# pir.net
KiCad netlist of a schematic drawn in EAGLE
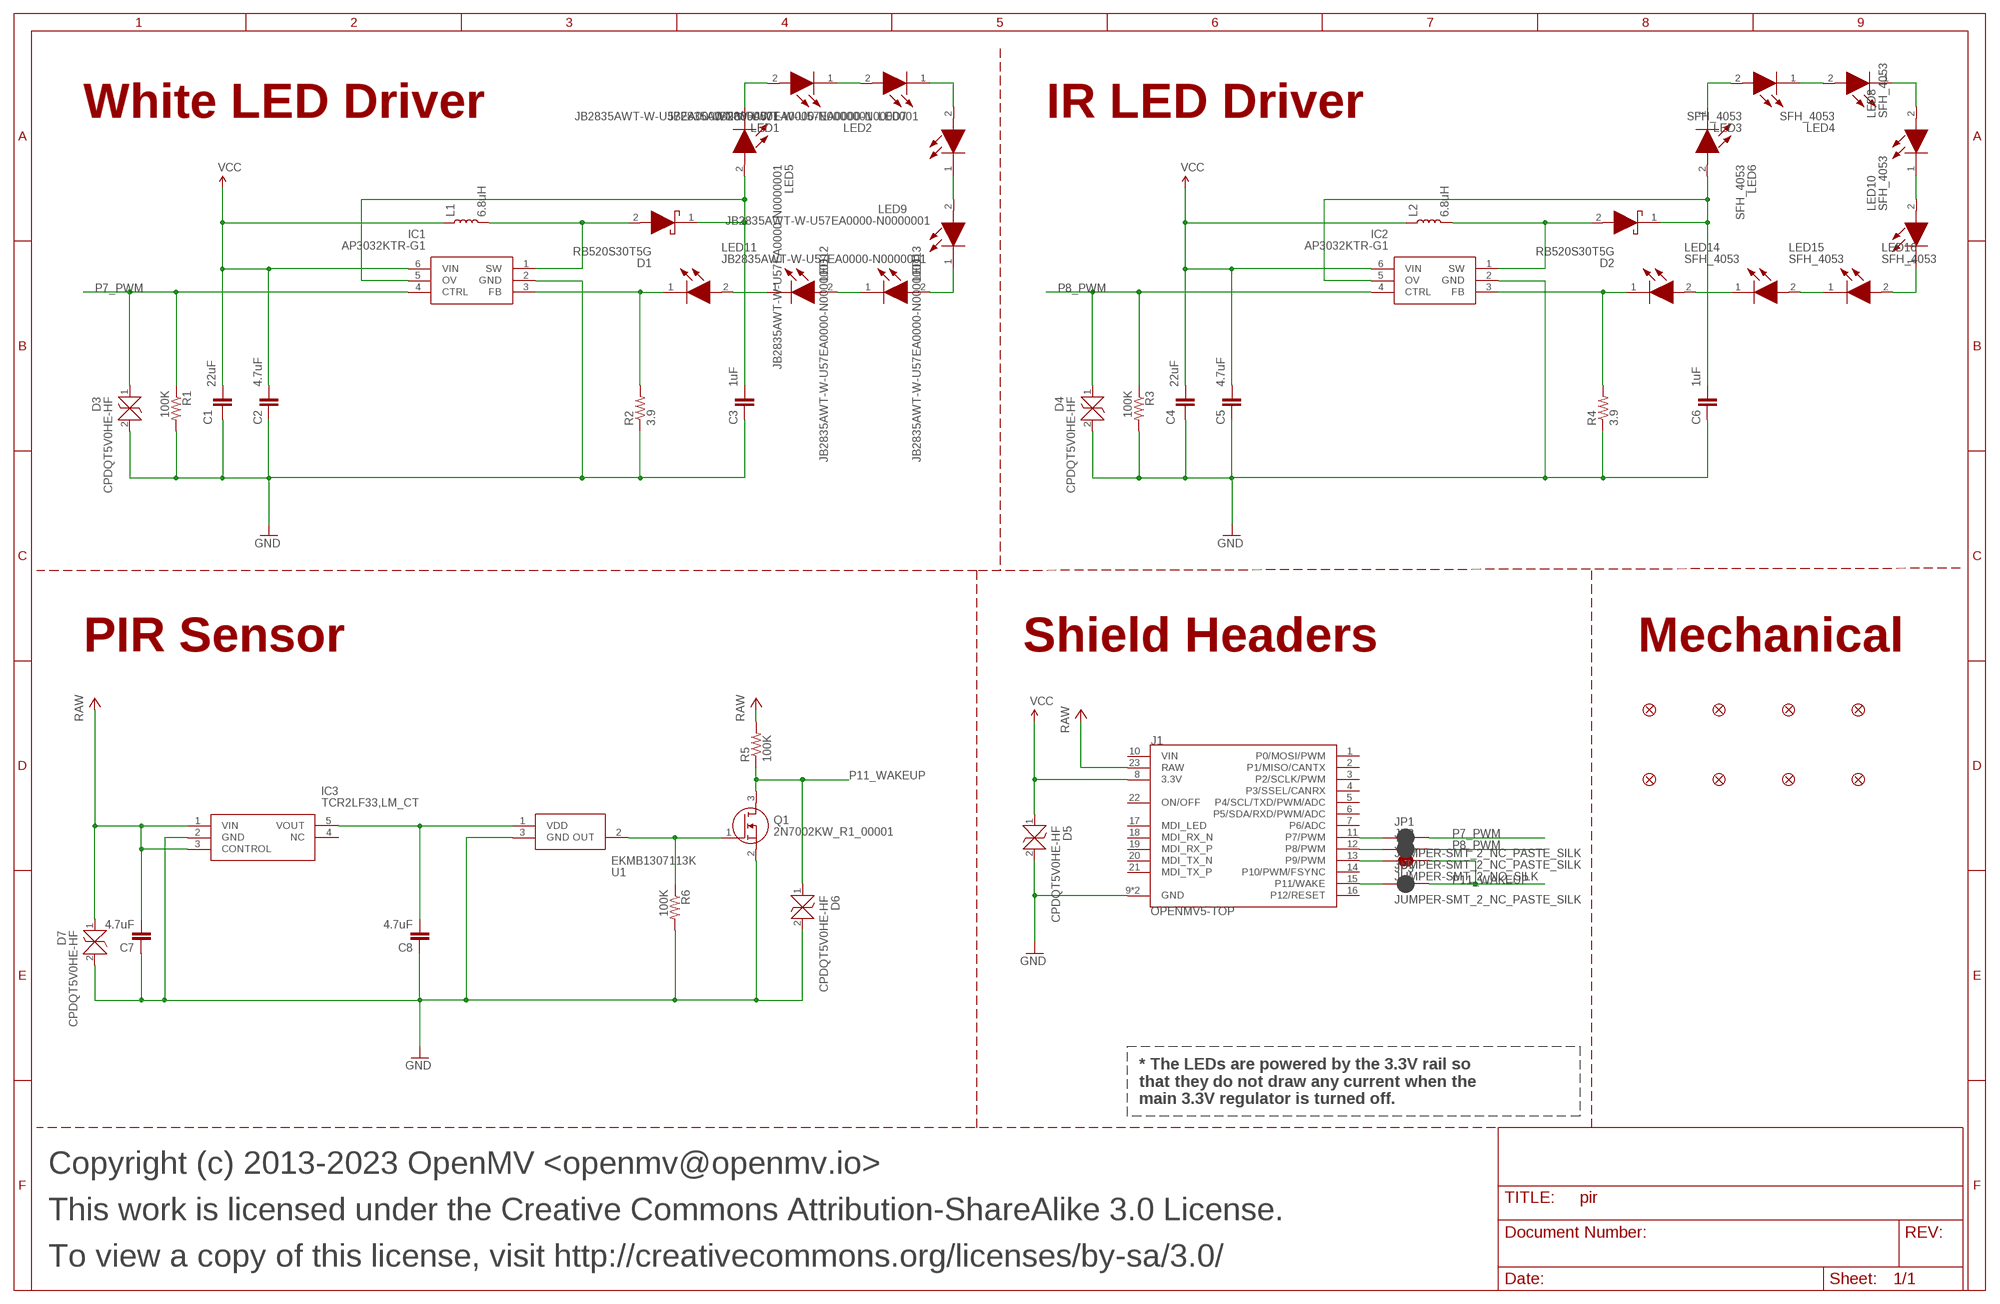
[diagram p0: schematic, sheet 1]

(export (version "E")
  (design (tool "Eeschema 10.0.6"))
  (components
    (comp (ref "C1")
      (value "22uF")
      (footprint "eagle-import:0805")
      (fields (field (name "MPN") "CL21A226MQQNNNE"))
      (libsource (lib "eagle-import") (part "22UF-0805-6.3V-20%"))
    )
    (comp (ref "C2")
      (value "4.7uF")
      (footprint "eagle-import:0402-CAP")
      (fields (field (name "MPN") "JMK105BBJ475MV-F"))
      (libsource (lib "eagle-import") (part "CAP0402-CAP"))
    )
    (comp (ref "C3")
      (value "1uF")
      (footprint "eagle-import:0402-CAP")
      (fields (field (name "MPN") "GRM155R6YA105KE11D"))
      (libsource (lib "eagle-import") (part "CAP0402-CAP"))
    )
    (comp (ref "C4")
      (value "22uF")
      (footprint "eagle-import:0805")
      (fields (field (name "MPN") "CL21A226MQQNNNE"))
      (libsource (lib "eagle-import") (part "22UF-0805-6.3V-20%"))
    )
    (comp (ref "C5")
      (value "4.7uF")
      (footprint "eagle-import:0402-CAP")
      (fields (field (name "MPN") "JMK105BBJ475MV-F"))
      (libsource (lib "eagle-import") (part "CAP0402-CAP"))
    )
    (comp (ref "C6")
      (value "1uF")
      (footprint "eagle-import:0402-CAP")
      (fields (field (name "MPN") "GRM155R6YA105KE11D"))
      (libsource (lib "eagle-import") (part "CAP0402-CAP"))
    )
    (comp (ref "C7")
      (value "4.7uF")
      (footprint "eagle-import:0402-CAP")
      (fields (field (name "MPN") "JMK105BBJ475MV-F"))
      (libsource (lib "eagle-import") (part "CAP0402-CAP"))
    )
    (comp (ref "C8")
      (value "4.7uF")
      (footprint "eagle-import:0402-CAP")
      (fields (field (name "MPN") "JMK105BBJ475MV-F"))
      (libsource (lib "eagle-import") (part "CAP0402-CAP"))
    )
    (comp (ref "D1")
      (value "RB520S30T5G")
      (footprint "eagle-import:SODFL1608X70N")
      (fields (field (name "MOUSER_PART_NUMBER") "863-RB520S30T5G"))
      (libsource (lib "eagle-import") (part "RB520S30T5G"))
    )
    (comp (ref "D2")
      (value "RB520S30T5G")
      (footprint "eagle-import:SODFL1608X70N")
      (fields (field (name "MOUSER_PART_NUMBER") "863-RB520S30T5G"))
      (libsource (lib "eagle-import") (part "RB520S30T5G"))
    )
    (comp (ref "D3")
      (value "CPDQT5V0HE-HF")
      (footprint "eagle-import:CPDQT5V0HEHF")
      (libsource (lib "eagle-import") (part "CPDQT5V0HE-HF"))
    )
    (comp (ref "D4")
      (value "CPDQT5V0HE-HF")
      (footprint "eagle-import:CPDQT5V0HEHF")
      (libsource (lib "eagle-import") (part "CPDQT5V0HE-HF"))
    )
    (comp (ref "D5")
      (value "CPDQT5V0HE-HF")
      (footprint "eagle-import:CPDQT5V0HEHF")
      (libsource (lib "eagle-import") (part "CPDQT5V0HE-HF"))
    )
    (comp (ref "D6")
      (value "CPDQT5V0HE-HF")
      (footprint "eagle-import:CPDQT5V0HEHF")
      (libsource (lib "eagle-import") (part "CPDQT5V0HE-HF"))
    )
    (comp (ref "D7")
      (value "CPDQT5V0HE-HF")
      (footprint "eagle-import:CPDQT5V0HEHF")
      (libsource (lib "eagle-import") (part "CPDQT5V0HE-HF"))
    )
    (comp (ref "FD1")
      (value "FIDUCIAL1X2")
      (footprint "eagle-import:FIDUCIAL-1X2")
      (libsource (lib "eagle-import") (part "FIDUCIAL1X2"))
    )
    (comp (ref "FD2")
      (value "FIDUCIAL1X2")
      (footprint "eagle-import:FIDUCIAL-1X2")
      (libsource (lib "eagle-import") (part "FIDUCIAL1X2"))
    )
    (comp (ref "FD3")
      (value "FIDUCIAL1X2")
      (footprint "eagle-import:FIDUCIAL-1X2")
      (libsource (lib "eagle-import") (part "FIDUCIAL1X2"))
    )
    (comp (ref "FD4")
      (value "FIDUCIAL1X2")
      (footprint "eagle-import:FIDUCIAL-1X2")
      (libsource (lib "eagle-import") (part "FIDUCIAL1X2"))
    )
    (comp (ref "FD5")
      (value "FIDUCIAL1X2")
      (footprint "eagle-import:FIDUCIAL-1X2")
      (libsource (lib "eagle-import") (part "FIDUCIAL1X2"))
    )
    (comp (ref "FD6")
      (value "FIDUCIAL1X2")
      (footprint "eagle-import:FIDUCIAL-1X2")
      (libsource (lib "eagle-import") (part "FIDUCIAL1X2"))
    )
    (comp (ref "FD7")
      (value "FIDUCIAL1X2")
      (footprint "eagle-import:FIDUCIAL-1X2")
      (libsource (lib "eagle-import") (part "FIDUCIAL1X2"))
    )
    (comp (ref "FD8")
      (value "FIDUCIAL1X2")
      (footprint "eagle-import:FIDUCIAL-1X2")
      (libsource (lib "eagle-import") (part "FIDUCIAL1X2"))
    )
    (comp (ref "IC1")
      (value "AP3032KTR-G1")
      (footprint "eagle-import:SOT95P280X145-6N")
      (fields (field (name "MOUSER_PART_NUMBER") "621-AP3032KTR-G1"))
      (libsource (lib "eagle-import") (part "AP3032KTR-G1"))
    )
    (comp (ref "IC2")
      (value "AP3032KTR-G1")
      (footprint "eagle-import:SOT95P280X145-6N")
      (fields (field (name "MOUSER_PART_NUMBER") "621-AP3032KTR-G1"))
      (libsource (lib "eagle-import") (part "AP3032KTR-G1"))
    )
    (comp (ref "IC3")
      (value "TCR2LF33,LM_CT")
      (footprint "eagle-import:TCR2LF33LMCT")
      (fields
        (field (name "MANUFACTURER_PART_NUMBER") "TCR2LF33,LM(CT")
        (field (name "MOUSER_PART_NUMBER") "757-TCR2LF33LMCT")
      )
      (libsource (lib "eagle-import") (part "TCR2LF33,LM_CT"))
    )
    (comp (ref "J1")
      (value "OPENMV5-TOP")
      (footprint "eagle-import:OPENMV5-TOP")
      (libsource (lib "eagle-import") (part "OPENMV5-TOP"))
    )
    (comp (ref "JP1")
      (value "JUMPER-SMT_2_NC_PASTE_SILK")
      (footprint "eagle-import:SMT-JUMPER_2_NC_PASTE_SILK")
      (libsource (lib "eagle-import") (part "JUMPER-SMT_2_NC_PASTE_SILK"))
    )
    (comp (ref "JP2")
      (value "JUMPER-SMT_2_NC_PASTE_SILK")
      (footprint "eagle-import:SMT-JUMPER_2_NC_PASTE_SILK")
      (libsource (lib "eagle-import") (part "JUMPER-SMT_2_NC_PASTE_SILK"))
    )
    (comp (ref "JP3")
      (value "JUMPER-SMT_2_NC_PASTE_SILK")
      (footprint "eagle-import:SMT-JUMPER_2_NC_PASTE_SILK")
      (libsource (lib "eagle-import") (part "JUMPER-SMT_2_NC_PASTE_SILK"))
    )
    (comp (ref "JP4")
      (value "JUMPER-SMT_2_NO_SILK")
      (footprint "eagle-import:SMT-JUMPER_2_NO_SILK")
      (libsource (lib "eagle-import") (part "JUMPER-SMT_2_NO_SILK"))
    )
    (comp (ref "L1")
      (value "6.8uH")
      (footprint "eagle-import:0805")
      (fields (field (name "MPN") "MLZ2012M6R8WT000"))
      (libsource (lib "eagle-import") (part "INDUCTOR-0805-3.3UH"))
    )
    (comp (ref "L2")
      (value "6.8uH")
      (footprint "eagle-import:0805")
      (fields (field (name "MPN") "MLZ2012M6R8WT000"))
      (libsource (lib "eagle-import") (part "INDUCTOR-0805-3.3UH"))
    )
    (comp (ref "LED1")
      (value "JB2835AWT-W-U57EA0000-N0000001")
      (footprint "eagle-import:JB2835AWTWU57EA0000N0000001")
      (fields (field (name "MOUSER_PART_NUMBER") "941-JB2835AWTU57EAN"))
      (libsource (lib "eagle-import") (part "JB2835AWT-W-U57EA0000-N0000001"))
    )
    (comp (ref "LED2")
      (value "JB2835AWT-W-U57EA0000-N0000001")
      (footprint "eagle-import:JB2835AWTWU57EA0000N0000001")
      (fields (field (name "MOUSER_PART_NUMBER") "941-JB2835AWTU57EAN"))
      (libsource (lib "eagle-import") (part "JB2835AWT-W-U57EA0000-N0000001"))
    )
    (comp (ref "LED3")
      (value "SFH_4053")
      (footprint "eagle-import:LEDC1005X55N")
      (fields
        (field (name "MANUFACTURER_PART_NUMBER") "SFH 4053")
        (field (name "MOUSER_PART_NUMBER") "720-SFH4053")
      )
      (libsource (lib "eagle-import") (part "SFH_4053"))
    )
    (comp (ref "LED4")
      (value "SFH_4053")
      (footprint "eagle-import:LEDC1005X55N")
      (fields
        (field (name "MANUFACTURER_PART_NUMBER") "SFH 4053")
        (field (name "MOUSER_PART_NUMBER") "720-SFH4053")
      )
      (libsource (lib "eagle-import") (part "SFH_4053"))
    )
    (comp (ref "LED5")
      (value "JB2835AWT-W-U57EA0000-N0000001")
      (footprint "eagle-import:JB2835AWTWU57EA0000N0000001")
      (fields (field (name "MOUSER_PART_NUMBER") "941-JB2835AWTU57EAN"))
      (libsource (lib "eagle-import") (part "JB2835AWT-W-U57EA0000-N0000001"))
    )
    (comp (ref "LED6")
      (value "SFH_4053")
      (footprint "eagle-import:LEDC1005X55N")
      (fields
        (field (name "MANUFACTURER_PART_NUMBER") "SFH 4053")
        (field (name "MOUSER_PART_NUMBER") "720-SFH4053")
      )
      (libsource (lib "eagle-import") (part "SFH_4053"))
    )
    (comp (ref "LED7")
      (value "JB2835AWT-W-U57EA0000-N0000001")
      (footprint "eagle-import:JB2835AWTWU57EA0000N0000001")
      (fields (field (name "MOUSER_PART_NUMBER") "941-JB2835AWTU57EAN"))
      (libsource (lib "eagle-import") (part "JB2835AWT-W-U57EA0000-N0000001"))
    )
    (comp (ref "LED8")
      (value "SFH_4053")
      (footprint "eagle-import:LEDC1005X55N")
      (fields
        (field (name "MANUFACTURER_PART_NUMBER") "SFH 4053")
        (field (name "MOUSER_PART_NUMBER") "720-SFH4053")
      )
      (libsource (lib "eagle-import") (part "SFH_4053"))
    )
    (comp (ref "LED9")
      (value "JB2835AWT-W-U57EA0000-N0000001")
      (footprint "eagle-import:JB2835AWTWU57EA0000N0000001")
      (fields (field (name "MOUSER_PART_NUMBER") "941-JB2835AWTU57EAN"))
      (libsource (lib "eagle-import") (part "JB2835AWT-W-U57EA0000-N0000001"))
    )
    (comp (ref "LED10")
      (value "SFH_4053")
      (footprint "eagle-import:LEDC1005X55N")
      (fields
        (field (name "MANUFACTURER_PART_NUMBER") "SFH 4053")
        (field (name "MOUSER_PART_NUMBER") "720-SFH4053")
      )
      (libsource (lib "eagle-import") (part "SFH_4053"))
    )
    (comp (ref "LED11")
      (value "JB2835AWT-W-U57EA0000-N0000001")
      (footprint "eagle-import:JB2835AWTWU57EA0000N0000001")
      (fields (field (name "MOUSER_PART_NUMBER") "941-JB2835AWTU57EAN"))
      (libsource (lib "eagle-import") (part "JB2835AWT-W-U57EA0000-N0000001"))
    )
    (comp (ref "LED12")
      (value "JB2835AWT-W-U57EA0000-N0000001")
      (footprint "eagle-import:JB2835AWTWU57EA0000N0000001")
      (fields (field (name "MOUSER_PART_NUMBER") "941-JB2835AWTU57EAN"))
      (libsource (lib "eagle-import") (part "JB2835AWT-W-U57EA0000-N0000001"))
    )
    (comp (ref "LED13")
      (value "JB2835AWT-W-U57EA0000-N0000001")
      (footprint "eagle-import:JB2835AWTWU57EA0000N0000001")
      (fields (field (name "MOUSER_PART_NUMBER") "941-JB2835AWTU57EAN"))
      (libsource (lib "eagle-import") (part "JB2835AWT-W-U57EA0000-N0000001"))
    )
    (comp (ref "LED14")
      (value "SFH_4053")
      (footprint "eagle-import:LEDC1005X55N")
      (fields
        (field (name "MANUFACTURER_PART_NUMBER") "SFH 4053")
        (field (name "MOUSER_PART_NUMBER") "720-SFH4053")
      )
      (libsource (lib "eagle-import") (part "SFH_4053"))
    )
    (comp (ref "LED15")
      (value "SFH_4053")
      (footprint "eagle-import:LEDC1005X55N")
      (fields
        (field (name "MANUFACTURER_PART_NUMBER") "SFH 4053")
        (field (name "MOUSER_PART_NUMBER") "720-SFH4053")
      )
      (libsource (lib "eagle-import") (part "SFH_4053"))
    )
    (comp (ref "LED16")
      (value "SFH_4053")
      (footprint "eagle-import:LEDC1005X55N")
      (fields
        (field (name "MANUFACTURER_PART_NUMBER") "SFH 4053")
        (field (name "MOUSER_PART_NUMBER") "720-SFH4053")
      )
      (libsource (lib "eagle-import") (part "SFH_4053"))
    )
    (comp (ref "Q1")
      (value "2N7002KW_R1_00001")
      (footprint "eagle-import:SOT65P210X110-3N")
      (fields (field (name "MOUSER_PART_NUMBER") "241-2N7002KWR100001"))
      (libsource (lib "eagle-import") (part "2N7002KW_R1_00001"))
    )
    (comp (ref "R1")
      (value "100K")
      (footprint "eagle-import:0402-RES")
      (fields (field (name "MPN") "AC0402FR-07100KL"))
      (libsource (lib "eagle-import") (part "RESISTOR0402-RES"))
    )
    (comp (ref "R2")
      (value "3.9")
      (footprint "eagle-import:R2512")
      (fields (field (name "MPN") "35203R9JT"))
      (libsource (lib "eagle-import") (part "R-US_R2512"))
    )
    (comp (ref "R3")
      (value "100K")
      (footprint "eagle-import:0402-RES")
      (fields (field (name "MPN") "AC0402FR-07100KL"))
      (libsource (lib "eagle-import") (part "RESISTOR0402-RES"))
    )
    (comp (ref "R4")
      (value "3.9")
      (footprint "eagle-import:R2512")
      (fields (field (name "MPN") "35203R9JT"))
      (libsource (lib "eagle-import") (part "R-US_R2512"))
    )
    (comp (ref "R5")
      (value "100K")
      (footprint "eagle-import:0402-RES")
      (fields (field (name "MPN") "AC0402FR-07100KL"))
      (libsource (lib "eagle-import") (part "RESISTOR0402-RES"))
    )
    (comp (ref "R6")
      (value "100K")
      (footprint "eagle-import:0402-RES")
      (fields (field (name "MPN") "AC0402FR-07100KL"))
      (libsource (lib "eagle-import") (part "RESISTOR0402-RES"))
    )
    (comp (ref "U1")
      (value "EKMB1307113K")
      (footprint "eagle-import:EKMB1304111K")
      (fields
        (field (name "MANUFACTURER_PART_NUMBER") "EKMB1304111K")
        (field (name "MOUSER_PART_NUMBER") "769-EKMB1304111K")
      )
      (libsource (lib "eagle-import") (part "EKMB1304111K"))
    )
  )
  (nets
    (net (code "1") (name "/P7_PWM") (class "Default")
      (node (ref "D3") (pin "1") (pinfunction "1_1") (pintype "bidirectional"))
      (node (ref "IC1") (pin "4") (pinfunction "CTRL_4") (pintype "bidirectional"))
      (node (ref "JP1") (pin "2") (pinfunction "2_2") (pintype "passive"))
      (node (ref "R1") (pin "1") (pinfunction "1_1") (pintype "passive"))
    )
    (net (code "2") (name "/P8_PWM") (class "Default")
      (node (ref "D4") (pin "1") (pinfunction "1_1") (pintype "bidirectional"))
      (node (ref "IC2") (pin "4") (pinfunction "CTRL_4") (pintype "bidirectional"))
      (node (ref "JP2") (pin "2") (pinfunction "2_2") (pintype "passive"))
      (node (ref "R3") (pin "1") (pinfunction "1_1") (pintype "passive"))
    )
    (net (code "3") (name "/P11_WAKEUP") (class "Default")
      (node (ref "D6") (pin "1") (pinfunction "1_1") (pintype "bidirectional"))
      (node (ref "JP3") (pin "2") (pinfunction "2_2") (pintype "passive"))
      (node (ref "JP4") (pin "2") (pinfunction "2_2") (pintype "passive"))
      (node (ref "Q1") (pin "3") (pinfunction "D_3") (pintype "bidirectional"))
      (node (ref "R5") (pin "1") (pinfunction "1_1") (pintype "passive"))
    )
    (net (code "4") (name "/VIN") (class "Default")
      (node (ref "J1") (pin "10") (pinfunction "VIN_10") (pintype "power_in"))
    )
    (net (code "5") (name "GND") (class "Default")
      (node (ref "C1") (pin "1") (pinfunction "1_1") (pintype "passive"))
      (node (ref "C2") (pin "1") (pinfunction "1_1") (pintype "passive"))
      (node (ref "C3") (pin "1") (pinfunction "1_1") (pintype "passive"))
      (node (ref "C4") (pin "1") (pinfunction "1_1") (pintype "passive"))
      (node (ref "C5") (pin "1") (pinfunction "1_1") (pintype "passive"))
      (node (ref "C6") (pin "1") (pinfunction "1_1") (pintype "passive"))
      (node (ref "C7") (pin "1") (pinfunction "1_1") (pintype "passive"))
      (node (ref "C8") (pin "1") (pinfunction "1_1") (pintype "passive"))
      (node (ref "D3") (pin "2") (pinfunction "2_2") (pintype "bidirectional"))
      (node (ref "D4") (pin "2") (pinfunction "2_2") (pintype "bidirectional"))
      (node (ref "D5") (pin "2") (pinfunction "2_2") (pintype "bidirectional"))
      (node (ref "D6") (pin "2") (pinfunction "2_2") (pintype "bidirectional"))
      (node (ref "D7") (pin "2") (pinfunction "2_2") (pintype "bidirectional"))
      (node (ref "IC1") (pin "2") (pinfunction "GND_2") (pintype "bidirectional"))
      (node (ref "IC2") (pin "2") (pinfunction "GND_2") (pintype "bidirectional"))
      (node (ref "IC3") (pin "2") (pinfunction "GND_2") (pintype "bidirectional"))
      (node (ref "J1") (pin "24") (pinfunction "GND_24") (pintype "power_in"))
      (node (ref "J1") (pin "9") (pinfunction "GND_9") (pintype "power_in"))
      (node (ref "Q1") (pin "2") (pinfunction "S_2") (pintype "bidirectional"))
      (node (ref "R1") (pin "2") (pinfunction "2_2") (pintype "passive"))
      (node (ref "R2") (pin "1") (pinfunction "1_1") (pintype "passive"))
      (node (ref "R3") (pin "2") (pinfunction "2_2") (pintype "passive"))
      (node (ref "R4") (pin "1") (pinfunction "1_1") (pintype "passive"))
      (node (ref "R6") (pin "2") (pinfunction "2_2") (pintype "passive"))
      (node (ref "U1") (pin "3") (pinfunction "GND_3") (pintype "bidirectional"))
    )
    (net (code "6") (name "Net-(D1-A)") (class "Default")
      (node (ref "D1") (pin "2") (pinfunction "A_2") (pintype "bidirectional"))
      (node (ref "IC1") (pin "1") (pinfunction "SW_1") (pintype "bidirectional"))
      (node (ref "L1") (pin "2") (pinfunction "2_2") (pintype "passive"))
    )
    (net (code "7") (name "Net-(D1-K)") (class "Default")
      (node (ref "C3") (pin "2") (pinfunction "2_2") (pintype "passive"))
      (node (ref "D1") (pin "1") (pinfunction "K_1") (pintype "bidirectional"))
      (node (ref "IC1") (pin "5") (pinfunction "OV_5") (pintype "bidirectional"))
      (node (ref "LED5") (pin "2") (pinfunction "A_2") (pintype "bidirectional"))
    )
    (net (code "8") (name "Net-(D2-A)") (class "Default")
      (node (ref "D2") (pin "2") (pinfunction "A_2") (pintype "bidirectional"))
      (node (ref "IC2") (pin "1") (pinfunction "SW_1") (pintype "bidirectional"))
      (node (ref "L2") (pin "2") (pinfunction "2_2") (pintype "passive"))
    )
    (net (code "9") (name "Net-(D2-K)") (class "Default")
      (node (ref "C6") (pin "2") (pinfunction "2_2") (pintype "passive"))
      (node (ref "D2") (pin "1") (pinfunction "K_1") (pintype "bidirectional"))
      (node (ref "IC2") (pin "5") (pinfunction "OV_5") (pintype "bidirectional"))
      (node (ref "LED6") (pin "2") (pinfunction "A_2") (pintype "bidirectional"))
    )
    (net (code "10") (name "Net-(IC1-FB)") (class "Default")
      (node (ref "IC1") (pin "3") (pinfunction "FB_3") (pintype "bidirectional"))
      (node (ref "LED11") (pin "1") (pinfunction "K_1") (pintype "bidirectional"))
      (node (ref "R2") (pin "2") (pinfunction "2_2") (pintype "passive"))
    )
    (net (code "11") (name "Net-(IC2-FB)") (class "Default")
      (node (ref "IC2") (pin "3") (pinfunction "FB_3") (pintype "bidirectional"))
      (node (ref "LED14") (pin "1") (pinfunction "K_1") (pintype "bidirectional"))
      (node (ref "R4") (pin "2") (pinfunction "2_2") (pintype "passive"))
    )
    (net (code "12") (name "Net-(IC3-VOUT)") (class "Default")
      (node (ref "C8") (pin "2") (pinfunction "2_2") (pintype "passive"))
      (node (ref "IC3") (pin "5") (pinfunction "VOUT_5") (pintype "bidirectional"))
      (node (ref "U1") (pin "1") (pinfunction "VDD_1") (pintype "bidirectional"))
    )
    (net (code "13") (name "Net-(J1-P7{slash}PWM)") (class "Default")
      (node (ref "J1") (pin "11") (pinfunction "P7/PWM_11") (pintype "bidirectional"))
      (node (ref "JP1") (pin "1") (pinfunction "1_1") (pintype "passive"))
    )
    (net (code "14") (name "Net-(J1-P8{slash}PWM)") (class "Default")
      (node (ref "J1") (pin "12") (pinfunction "P8/PWM_12") (pintype "bidirectional"))
      (node (ref "JP2") (pin "1") (pinfunction "1_1") (pintype "passive"))
    )
    (net (code "15") (name "Net-(J1-P9{slash}PWM)") (class "Default")
      (node (ref "J1") (pin "13") (pinfunction "P9/PWM_13") (pintype "bidirectional"))
      (node (ref "JP4") (pin "1") (pinfunction "1_1") (pintype "passive"))
    )
    (net (code "16") (name "Net-(J1-P11{slash}WAKE)") (class "Default")
      (node (ref "J1") (pin "15") (pinfunction "P11/WAKE_15") (pintype "bidirectional"))
      (node (ref "JP3") (pin "1") (pinfunction "1_1") (pintype "passive"))
    )
    (net (code "17") (name "Net-(LED1-A)") (class "Default")
      (node (ref "LED1") (pin "2") (pinfunction "A_2") (pintype "bidirectional"))
      (node (ref "LED5") (pin "1") (pinfunction "K_1") (pintype "bidirectional"))
    )
    (net (code "18") (name "Net-(LED1-K)") (class "Default")
      (node (ref "LED1") (pin "1") (pinfunction "K_1") (pintype "bidirectional"))
      (node (ref "LED2") (pin "2") (pinfunction "A_2") (pintype "bidirectional"))
    )
    (net (code "19") (name "Net-(LED2-K)") (class "Default")
      (node (ref "LED2") (pin "1") (pinfunction "K_1") (pintype "bidirectional"))
      (node (ref "LED7") (pin "2") (pinfunction "A_2") (pintype "bidirectional"))
    )
    (net (code "20") (name "Net-(LED3-A)") (class "Default")
      (node (ref "LED3") (pin "2") (pinfunction "A_2") (pintype "bidirectional"))
      (node (ref "LED6") (pin "1") (pinfunction "K_1") (pintype "bidirectional"))
    )
    (net (code "21") (name "Net-(LED3-K)") (class "Default")
      (node (ref "LED3") (pin "1") (pinfunction "K_1") (pintype "bidirectional"))
      (node (ref "LED4") (pin "2") (pinfunction "A_2") (pintype "bidirectional"))
    )
    (net (code "22") (name "Net-(LED4-K)") (class "Default")
      (node (ref "LED4") (pin "1") (pinfunction "K_1") (pintype "bidirectional"))
      (node (ref "LED8") (pin "2") (pinfunction "A_2") (pintype "bidirectional"))
    )
    (net (code "23") (name "Net-(LED7-K)") (class "Default")
      (node (ref "LED7") (pin "1") (pinfunction "K_1") (pintype "bidirectional"))
      (node (ref "LED9") (pin "2") (pinfunction "A_2") (pintype "bidirectional"))
    )
    (net (code "24") (name "Net-(LED10-A)") (class "Default")
      (node (ref "LED10") (pin "2") (pinfunction "A_2") (pintype "bidirectional"))
      (node (ref "LED8") (pin "1") (pinfunction "K_1") (pintype "bidirectional"))
    )
    (net (code "25") (name "Net-(LED10-K)") (class "Default")
      (node (ref "LED10") (pin "1") (pinfunction "K_1") (pintype "bidirectional"))
      (node (ref "LED16") (pin "2") (pinfunction "A_2") (pintype "bidirectional"))
    )
    (net (code "26") (name "Net-(LED11-A)") (class "Default")
      (node (ref "LED11") (pin "2") (pinfunction "A_2") (pintype "bidirectional"))
      (node (ref "LED12") (pin "1") (pinfunction "K_1") (pintype "bidirectional"))
    )
    (net (code "27") (name "Net-(LED12-A)") (class "Default")
      (node (ref "LED12") (pin "2") (pinfunction "A_2") (pintype "bidirectional"))
      (node (ref "LED13") (pin "1") (pinfunction "K_1") (pintype "bidirectional"))
    )
    (net (code "28") (name "Net-(LED13-A)") (class "Default")
      (node (ref "LED13") (pin "2") (pinfunction "A_2") (pintype "bidirectional"))
      (node (ref "LED9") (pin "1") (pinfunction "K_1") (pintype "bidirectional"))
    )
    (net (code "29") (name "Net-(LED14-A)") (class "Default")
      (node (ref "LED14") (pin "2") (pinfunction "A_2") (pintype "bidirectional"))
      (node (ref "LED15") (pin "1") (pinfunction "K_1") (pintype "bidirectional"))
    )
    (net (code "30") (name "Net-(LED15-A)") (class "Default")
      (node (ref "LED15") (pin "2") (pinfunction "A_2") (pintype "bidirectional"))
      (node (ref "LED16") (pin "1") (pinfunction "K_1") (pintype "bidirectional"))
    )
    (net (code "31") (name "Net-(Q1-G)") (class "Default")
      (node (ref "Q1") (pin "1") (pinfunction "G_1") (pintype "bidirectional"))
      (node (ref "R6") (pin "1") (pinfunction "1_1") (pintype "passive"))
      (node (ref "U1") (pin "2") (pinfunction "OUT_2") (pintype "bidirectional"))
    )
    (net (code "32") (name "RAW") (class "Default")
      (node (ref "C7") (pin "2") (pinfunction "2_2") (pintype "passive"))
      (node (ref "D7") (pin "1") (pinfunction "1_1") (pintype "bidirectional"))
      (node (ref "IC3") (pin "1") (pinfunction "VIN_1") (pintype "bidirectional"))
      (node (ref "IC3") (pin "3") (pinfunction "CONTROL_3") (pintype "bidirectional"))
      (node (ref "J1") (pin "23") (pinfunction "RAW_23") (pintype "power_in"))
      (node (ref "R5") (pin "2") (pinfunction "2_2") (pintype "passive"))
    )
    (net (code "33") (name "VCC") (class "Default")
      (node (ref "C1") (pin "2") (pinfunction "2_2") (pintype "passive"))
      (node (ref "C2") (pin "2") (pinfunction "2_2") (pintype "passive"))
      (node (ref "C4") (pin "2") (pinfunction "2_2") (pintype "passive"))
      (node (ref "C5") (pin "2") (pinfunction "2_2") (pintype "passive"))
      (node (ref "D5") (pin "1") (pinfunction "1_1") (pintype "bidirectional"))
      (node (ref "IC1") (pin "6") (pinfunction "VIN_6") (pintype "bidirectional"))
      (node (ref "IC2") (pin "6") (pinfunction "VIN_6") (pintype "bidirectional"))
      (node (ref "J1") (pin "8") (pinfunction "3.3V_8") (pintype "power_in"))
      (node (ref "L1") (pin "1") (pinfunction "1_1") (pintype "passive"))
      (node (ref "L2") (pin "1") (pinfunction "1_1") (pintype "passive"))
    )
    (net (code "34") (name "unconnected-(IC3-NC-Pad4)") (class "Default")
      (node (ref "IC3") (pin "4") (pinfunction "NC_4") (pintype "no_connect"))
    )
    (net (code "35") (name "unconnected-(J1-MDI_LED-Pad17)") (class "Default")
      (node (ref "J1") (pin "17") (pinfunction "MDI_LED_17") (pintype "bidirectional"))
    )
    (net (code "36") (name "unconnected-(J1-MDI_RX_N-Pad18)") (class "Default")
      (node (ref "J1") (pin "18") (pinfunction "MDI_RX_N_18") (pintype "bidirectional"))
    )
    (net (code "37") (name "unconnected-(J1-MDI_RX_P-Pad19)") (class "Default")
      (node (ref "J1") (pin "19") (pinfunction "MDI_RX_P_19") (pintype "bidirectional"))
    )
    (net (code "38") (name "unconnected-(J1-MDI_TX_N-Pad20)") (class "Default")
      (node (ref "J1") (pin "20") (pinfunction "MDI_TX_N_20") (pintype "bidirectional"))
    )
    (net (code "39") (name "unconnected-(J1-MDI_TX_P-Pad21)") (class "Default")
      (node (ref "J1") (pin "21") (pinfunction "MDI_TX_P_21") (pintype "bidirectional"))
    )
    (net (code "40") (name "unconnected-(J1-ON{slash}OFF-Pad22)") (class "Default")
      (node (ref "J1") (pin "22") (pinfunction "ON/OFF_22") (pintype "bidirectional"))
    )
    (net (code "41") (name "unconnected-(J1-P0{slash}MOSI{slash}PWM-Pad1)") (class "Default")
      (node (ref "J1") (pin "1") (pinfunction "P0/MOSI/PWM_1") (pintype "bidirectional"))
    )
    (net (code "42") (name "unconnected-(J1-P1{slash}MISO{slash}CANTX-Pad2)") (class "Default")
      (node (ref "J1") (pin "2") (pinfunction "P1/MISO/CANTX_2") (pintype "bidirectional"))
    )
    (net (code "43") (name "unconnected-(J1-P2{slash}SCLK{slash}PWM-Pad3)") (class "Default")
      (node (ref "J1") (pin "3") (pinfunction "P2/SCLK/PWM_3") (pintype "bidirectional"))
    )
    (net (code "44") (name "unconnected-(J1-P3{slash}SSEL{slash}CANRX-Pad4)") (class "Default")
      (node (ref "J1") (pin "4") (pinfunction "P3/SSEL/CANRX_4") (pintype "bidirectional"))
    )
    (net (code "45") (name "unconnected-(J1-P4{slash}SCL{slash}TXD{slash}PWM{slash}ADC-Pad5)") (class "Default")
      (node (ref "J1") (pin "5") (pinfunction "P4/SCL/TXD/PWM/ADC_5") (pintype "bidirectional"))
    )
    (net (code "46") (name "unconnected-(J1-P5{slash}SDA{slash}RXD{slash}PWM{slash}ADC-Pad6)") (class "Default")
      (node (ref "J1") (pin "6") (pinfunction "P5/SDA/RXD/PWM/ADC_6") (pintype "bidirectional"))
    )
    (net (code "47") (name "unconnected-(J1-P6{slash}ADC-Pad7)") (class "Default")
      (node (ref "J1") (pin "7") (pinfunction "P6/ADC_7") (pintype "bidirectional"))
    )
    (net (code "48") (name "unconnected-(J1-P10{slash}PWM{slash}FSYNC-Pad14)") (class "Default")
      (node (ref "J1") (pin "14") (pinfunction "P10/PWM/FSYNC_14") (pintype "bidirectional"))
    )
    (net (code "49") (name "unconnected-(J1-P12{slash}RESET-Pad16)") (class "Default")
      (node (ref "J1") (pin "16") (pinfunction "P12/RESET_16") (pintype "bidirectional"))
    )
  )
)
